# Final_MG.net
KiCad netlist of a schematic drawn in EAGLE
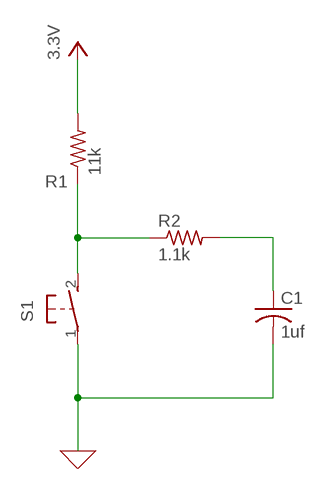
[diagram p0: schematic, sheet 1]

(export (version "E")
  (design (tool "Eeschema 10.0.6"))
  (components
    (comp (ref "C1")
      (value "1uf")
      (footprint "eagle-import:C025-024X044")
      (libsource (lib "eagle-import") (part "C-US025-024X044"))
    )
    (comp (ref "R1")
      (value "11k")
      (footprint "eagle-import:0204V")
      (libsource (lib "eagle-import") (part "R-US_0204/2V"))
    )
    (comp (ref "R2")
      (value "1.1k")
      (footprint "eagle-import:0204V")
      (libsource (lib "eagle-import") (part "R-US_0204/2V"))
    )
    (comp (ref "S1")
      (value "31-XX")
      (footprint "eagle-import:B3F-31XX")
      (fields (field (name "MPN") "B3F-3100"))
      (libsource (lib "eagle-import") (part "31-XX"))
    )
  )
  (nets
    (net (code "1") (name "3.3V") (class "Default")
      (node (ref "R1") (pin "2") (pinfunction "2_2") (pintype "passive"))
    )
    (net (code "2") (name "GND") (class "Default")
      (node (ref "C1") (pin "2") (pinfunction "2_2") (pintype "passive"))
      (node (ref "S1") (pin "1") (pinfunction "P_1") (pintype "passive"))
    )
    (net (code "3") (name "Net-(C1-Pad1)") (class "Default")
      (node (ref "C1") (pin "1") (pinfunction "1_1") (pintype "passive"))
      (node (ref "R2") (pin "2") (pinfunction "2_2") (pintype "passive"))
    )
    (net (code "4") (name "Net-(S1-S)") (class "Default")
      (node (ref "R1") (pin "1") (pinfunction "1_1") (pintype "passive"))
      (node (ref "R2") (pin "1") (pinfunction "1_1") (pintype "passive"))
      (node (ref "S1") (pin "2") (pinfunction "S_2") (pintype "passive"))
    )
  )
)
